# RelayCard.net
KiCad netlist of a schematic drawn in Altium Designer
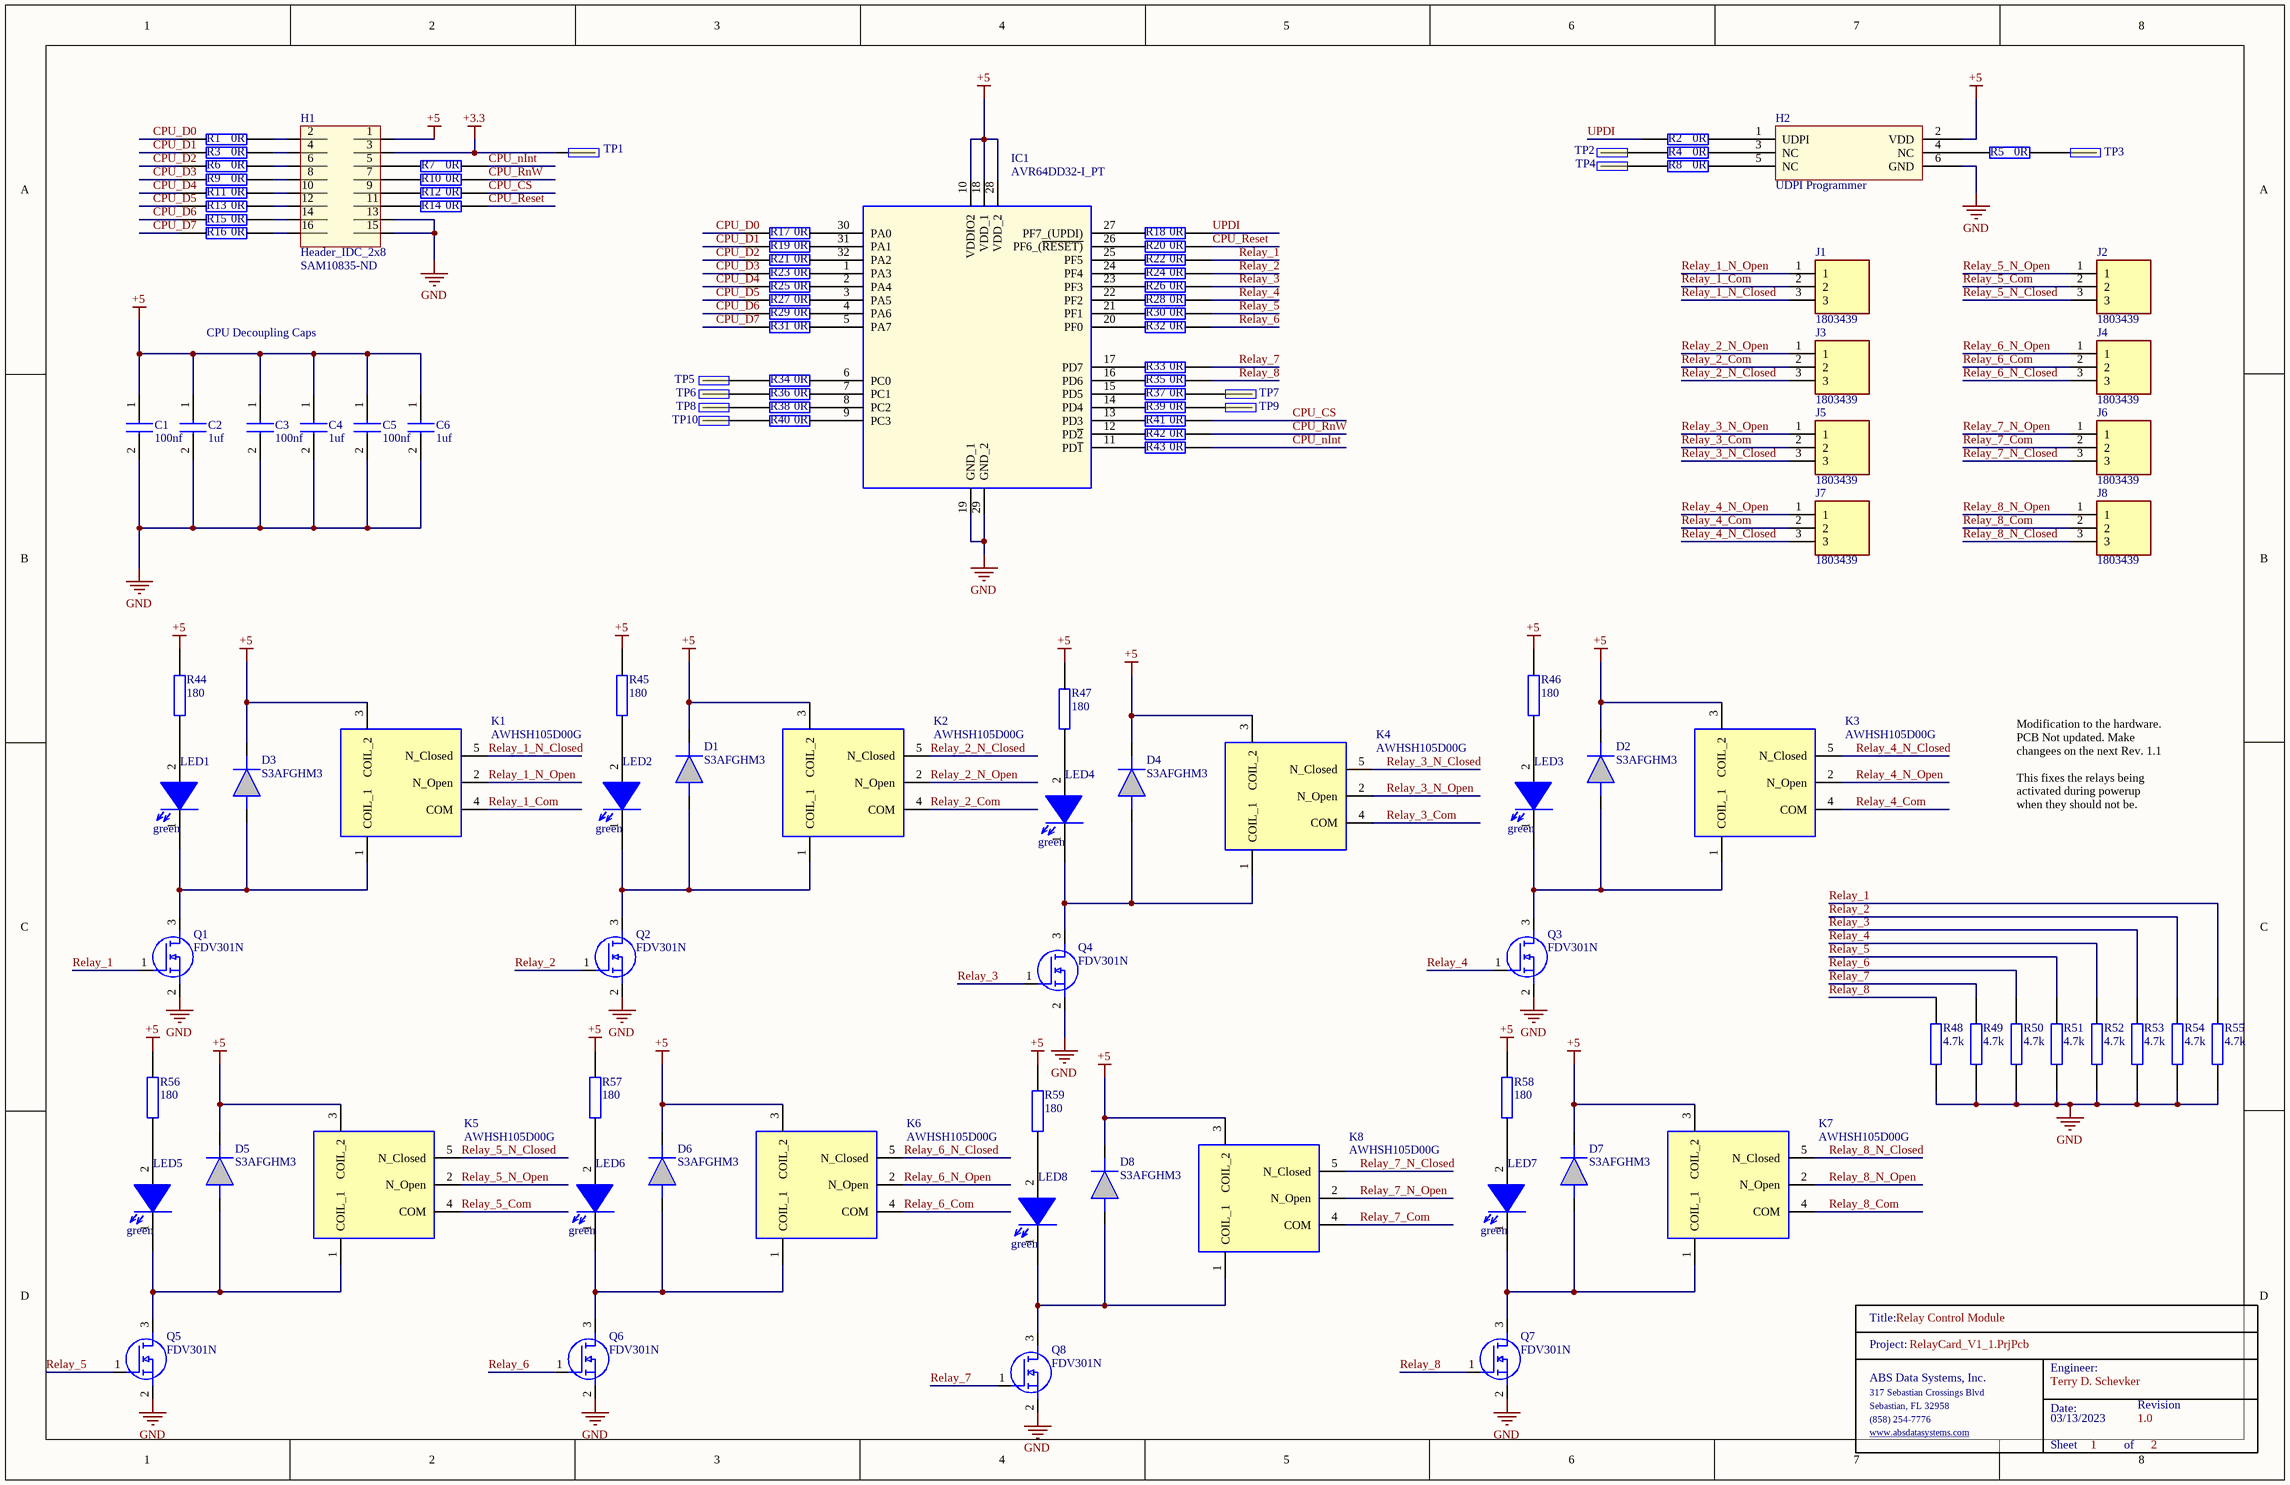
[diagram p0: RelayCard.SchDoc]

(export (version "E")
  (design (tool "Eeschema 10.0.6"))
  (components
    (comp (ref "C1")
      (value "100nf")
      (footprint "0603")
      (description "Samsung Electro-Mechanics 0603 100nf")
      (libsource (lib "Capacitors") (part "CL10B104JB8NNNC"))
    )
    (comp (ref "C2")
      (value "1uf")
      (footprint "0603")
      (description "Samsung Electro-Mechanics 0603 1uf")
      (libsource (lib "Capacitors") (part "CL10B105KA8NNNL"))
    )
    (comp (ref "C3")
      (value "100nf")
      (footprint "0603")
      (description "Samsung Electro-Mechanics 0603 100nf")
      (libsource (lib "Capacitors") (part "CL10B104JB8NNNC"))
    )
    (comp (ref "C4")
      (value "1uf")
      (footprint "0603")
      (description "Samsung Electro-Mechanics 0603 1uf")
      (libsource (lib "Capacitors") (part "CL10B105KA8NNNL"))
    )
    (comp (ref "C5")
      (value "100nf")
      (footprint "0603")
      (description "Samsung Electro-Mechanics 0603 100nf")
      (libsource (lib "Capacitors") (part "CL10B104JB8NNNC"))
    )
    (comp (ref "C6")
      (value "1uf")
      (footprint "0603")
      (description "Samsung Electro-Mechanics 0603 1uf")
      (libsource (lib "Capacitors") (part "CL10B105KA8NNNL"))
    )
    (comp (ref "D1")
      (value "S3AFGHM3")
      (footprint "DO-221AC")
      (description "Rectifiers VR=400V, IO=3A")
      (fields
        (field (name "MOUSER PART NUMBER") "750-1N4001-G")
        (field (name "MANUFACTURER_PART_NUMBER") "1N4001-G")
      )
      (libsource (lib "SemiConductors") (part "S3AFGHM3/I"))
    )
    (comp (ref "D2")
      (value "S3AFGHM3")
      (footprint "DO-221AC")
      (description "Rectifiers VR=400V, IO=3A")
      (fields
        (field (name "MOUSER PART NUMBER") "750-1N4001-G")
        (field (name "MANUFACTURER_PART_NUMBER") "1N4001-G")
      )
      (libsource (lib "SemiConductors") (part "S3AFGHM3/I"))
    )
    (comp (ref "D3")
      (value "S3AFGHM3")
      (footprint "DO-221AC")
      (description "Rectifiers VR=400V, IO=3A")
      (fields
        (field (name "MOUSER PART NUMBER") "750-1N4001-G")
        (field (name "MANUFACTURER_PART_NUMBER") "1N4001-G")
      )
      (libsource (lib "SemiConductors") (part "S3AFGHM3/I"))
    )
    (comp (ref "D4")
      (value "S3AFGHM3")
      (footprint "DO-221AC")
      (description "Rectifiers VR=400V, IO=3A")
      (fields
        (field (name "MOUSER PART NUMBER") "750-1N4001-G")
        (field (name "MANUFACTURER_PART_NUMBER") "1N4001-G")
      )
      (libsource (lib "SemiConductors") (part "S3AFGHM3/I"))
    )
    (comp (ref "D5")
      (value "S3AFGHM3")
      (footprint "DO-221AC")
      (description "Rectifiers VR=400V, IO=3A")
      (fields
        (field (name "MOUSER PART NUMBER") "750-1N4001-G")
        (field (name "MANUFACTURER_PART_NUMBER") "1N4001-G")
      )
      (libsource (lib "SemiConductors") (part "S3AFGHM3/I"))
    )
    (comp (ref "D6")
      (value "S3AFGHM3")
      (footprint "DO-221AC")
      (description "Rectifiers VR=400V, IO=3A")
      (fields
        (field (name "MOUSER PART NUMBER") "750-1N4001-G")
        (field (name "MANUFACTURER_PART_NUMBER") "1N4001-G")
      )
      (libsource (lib "SemiConductors") (part "S3AFGHM3/I"))
    )
    (comp (ref "D7")
      (value "S3AFGHM3")
      (footprint "DO-221AC")
      (description "Rectifiers VR=400V, IO=3A")
      (fields
        (field (name "MOUSER PART NUMBER") "750-1N4001-G")
        (field (name "MANUFACTURER_PART_NUMBER") "1N4001-G")
      )
      (libsource (lib "SemiConductors") (part "S3AFGHM3/I"))
    )
    (comp (ref "D8")
      (value "S3AFGHM3")
      (footprint "DO-221AC")
      (description "Rectifiers VR=400V, IO=3A")
      (fields
        (field (name "MOUSER PART NUMBER") "750-1N4001-G")
        (field (name "MANUFACTURER_PART_NUMBER") "1N4001-G")
      )
      (libsource (lib "SemiConductors") (part "S3AFGHM3/I"))
    )
    (comp (ref "H1")
      (value "Header_IDC_2x8")
      (footprint "HEADER16")
      (description "16 Pin 2x8 Through Hold IDC Connector")
      (fields
        (field (name "MANUFACTURER") "Samtec")
        (field (name "MANUFACTURER PART NUMBER") "TST-108-01-G-D")
        (field (name "SUPPLIER PART NUMBER 1") "SAM10835-ND")
      )
      (libsource (lib "Misc") (part "Header_IDC_2x8"))
    )
    (comp (ref "H2")
      (value "UDPI Programmer")
      (footprint "HDR2X3")
      (description "6 Pin 2X3 Through Hole Header")
      (libsource (lib "Misc") (part "UDPI Programmer"))
    )
    (comp (ref "IC1")
      (value "AVR64DD32-I_PT")
      (footprint "CPU_Memory:QFP80P900X900X120-32N")
      (description "Integrated Circuit")
      (fields (field (name "MANUFACTURER_PART_NUMBER") "AVR64DD32-I/PT ¦ MULTI-VOLTAGE I/O"))
      (libsource (lib "CPU_Memory") (part "AVR64DD32-I_PT"))
    )
    (comp (ref "J1")
      (value "1803439")
      (footprint "SamacSys:1803439")
      (description "Connector")
      (fields (field (name "MOUSER PART NUMBER") "651-1803439"))
      (libsource (lib "*") (part "1803439"))
    )
    (comp (ref "J2")
      (value "1803439")
      (footprint "SamacSys:1803439")
      (description "Connector")
      (fields (field (name "MOUSER PART NUMBER") "651-1803439"))
      (libsource (lib "*") (part "1803439"))
    )
    (comp (ref "J3")
      (value "1803439")
      (footprint "SamacSys:1803439")
      (description "Connector")
      (fields (field (name "MOUSER PART NUMBER") "651-1803439"))
      (libsource (lib "*") (part "1803439"))
    )
    (comp (ref "J4")
      (value "1803439")
      (footprint "SamacSys:1803439")
      (description "Connector")
      (fields (field (name "MOUSER PART NUMBER") "651-1803439"))
      (libsource (lib "*") (part "1803439"))
    )
    (comp (ref "J5")
      (value "1803439")
      (footprint "SamacSys:1803439")
      (description "Connector")
      (fields (field (name "MOUSER PART NUMBER") "651-1803439"))
      (libsource (lib "*") (part "1803439"))
    )
    (comp (ref "J6")
      (value "1803439")
      (footprint "SamacSys:1803439")
      (description "Connector")
      (fields (field (name "MOUSER PART NUMBER") "651-1803439"))
      (libsource (lib "*") (part "1803439"))
    )
    (comp (ref "J7")
      (value "1803439")
      (footprint "SamacSys:1803439")
      (description "Connector")
      (fields (field (name "MOUSER PART NUMBER") "651-1803439"))
      (libsource (lib "*") (part "1803439"))
    )
    (comp (ref "J8")
      (value "1803439")
      (footprint "SamacSys:1803439")
      (description "Connector")
      (fields (field (name "MOUSER PART NUMBER") "651-1803439"))
      (libsource (lib "*") (part "1803439"))
    )
    (comp (ref "K1")
      (value "AWHSH105D00G")
      (footprint "AWHSH105D00G")
      (fields (field (name "MOUSER PART NUMBER") "523-AWHSH105D00G"))
      (libsource (lib "Misc") (part "AWHSH105D00G"))
    )
    (comp (ref "K2")
      (value "AWHSH105D00G")
      (footprint "AWHSH105D00G")
      (fields (field (name "MOUSER PART NUMBER") "523-AWHSH105D00G"))
      (libsource (lib "Misc") (part "AWHSH105D00G"))
    )
    (comp (ref "K3")
      (value "AWHSH105D00G")
      (footprint "AWHSH105D00G")
      (fields (field (name "MOUSER PART NUMBER") "523-AWHSH105D00G"))
      (libsource (lib "Misc") (part "AWHSH105D00G"))
    )
    (comp (ref "K4")
      (value "AWHSH105D00G")
      (footprint "AWHSH105D00G")
      (fields (field (name "MOUSER PART NUMBER") "523-AWHSH105D00G"))
      (libsource (lib "Misc") (part "AWHSH105D00G"))
    )
    (comp (ref "K5")
      (value "AWHSH105D00G")
      (footprint "AWHSH105D00G")
      (fields (field (name "MOUSER PART NUMBER") "523-AWHSH105D00G"))
      (libsource (lib "Misc") (part "AWHSH105D00G"))
    )
    (comp (ref "K6")
      (value "AWHSH105D00G")
      (footprint "AWHSH105D00G")
      (fields (field (name "MOUSER PART NUMBER") "523-AWHSH105D00G"))
      (libsource (lib "Misc") (part "AWHSH105D00G"))
    )
    (comp (ref "K7")
      (value "AWHSH105D00G")
      (footprint "AWHSH105D00G")
      (fields (field (name "MOUSER PART NUMBER") "523-AWHSH105D00G"))
      (libsource (lib "Misc") (part "AWHSH105D00G"))
    )
    (comp (ref "K8")
      (value "AWHSH105D00G")
      (footprint "AWHSH105D00G")
      (fields (field (name "MOUSER PART NUMBER") "523-AWHSH105D00G"))
      (libsource (lib "Misc") (part "AWHSH105D00G"))
    )
    (comp (ref "LED1")
      (value "green")
      (footprint "0603_Diode")
      (description "Wurth Elektronik 0603 green")
      (fields
        (field (name "MANUFACTURER") "Wurth Electronics")
        (field (name "MANUFACTURER PART NUMBER") "150060GS75000")
      )
      (libsource (lib "Misc") (part "150060GS75000"))
    )
    (comp (ref "LED2")
      (value "green")
      (footprint "0603_Diode")
      (description "Wurth Elektronik 0603 green")
      (fields
        (field (name "MANUFACTURER") "Wurth Electronics")
        (field (name "MANUFACTURER PART NUMBER") "150060GS75000")
      )
      (libsource (lib "Misc") (part "150060GS75000"))
    )
    (comp (ref "LED3")
      (value "green")
      (footprint "0603_Diode")
      (description "Wurth Elektronik 0603 green")
      (fields
        (field (name "MANUFACTURER") "Wurth Electronics")
        (field (name "MANUFACTURER PART NUMBER") "150060GS75000")
      )
      (libsource (lib "Misc") (part "150060GS75000"))
    )
    (comp (ref "LED4")
      (value "green")
      (footprint "0603_Diode")
      (description "Wurth Elektronik 0603 green")
      (fields
        (field (name "MANUFACTURER") "Wurth Electronics")
        (field (name "MANUFACTURER PART NUMBER") "150060GS75000")
      )
      (libsource (lib "Misc") (part "150060GS75000"))
    )
    (comp (ref "LED5")
      (value "green")
      (footprint "0603_Diode")
      (description "Wurth Elektronik 0603 green")
      (fields
        (field (name "MANUFACTURER") "Wurth Electronics")
        (field (name "MANUFACTURER PART NUMBER") "150060GS75000")
      )
      (libsource (lib "Misc") (part "150060GS75000"))
    )
    (comp (ref "LED6")
      (value "green")
      (footprint "0603_Diode")
      (description "Wurth Elektronik 0603 green")
      (fields
        (field (name "MANUFACTURER") "Wurth Electronics")
        (field (name "MANUFACTURER PART NUMBER") "150060GS75000")
      )
      (libsource (lib "Misc") (part "150060GS75000"))
    )
    (comp (ref "LED7")
      (value "green")
      (footprint "0603_Diode")
      (description "Wurth Elektronik 0603 green")
      (fields
        (field (name "MANUFACTURER") "Wurth Electronics")
        (field (name "MANUFACTURER PART NUMBER") "150060GS75000")
      )
      (libsource (lib "Misc") (part "150060GS75000"))
    )
    (comp (ref "LED8")
      (value "green")
      (footprint "0603_Diode")
      (description "Wurth Elektronik 0603 green")
      (fields
        (field (name "MANUFACTURER") "Wurth Electronics")
        (field (name "MANUFACTURER PART NUMBER") "150060GS75000")
      )
      (libsource (lib "Misc") (part "150060GS75000"))
    )
    (comp (ref "Q1")
      (value "FDV301N")
      (footprint "SOT96P237X111-3N")
      (fields (field (name "MOUSER PART NUMBER") "512-FDV301N"))
      (libsource (lib "SemiConductors") (part "FDV301N"))
    )
    (comp (ref "Q2")
      (value "FDV301N")
      (footprint "SOT96P237X111-3N")
      (fields (field (name "MOUSER PART NUMBER") "512-FDV301N"))
      (libsource (lib "SemiConductors") (part "FDV301N"))
    )
    (comp (ref "Q3")
      (value "FDV301N")
      (footprint "SOT96P237X111-3N")
      (fields (field (name "MOUSER PART NUMBER") "512-FDV301N"))
      (libsource (lib "SemiConductors") (part "FDV301N"))
    )
    (comp (ref "Q4")
      (value "FDV301N")
      (footprint "SOT96P237X111-3N")
      (fields (field (name "MOUSER PART NUMBER") "512-FDV301N"))
      (libsource (lib "SemiConductors") (part "FDV301N"))
    )
    (comp (ref "Q5")
      (value "FDV301N")
      (footprint "SOT96P237X111-3N")
      (fields (field (name "MOUSER PART NUMBER") "512-FDV301N"))
      (libsource (lib "SemiConductors") (part "FDV301N"))
    )
    (comp (ref "Q6")
      (value "FDV301N")
      (footprint "SOT96P237X111-3N")
      (fields (field (name "MOUSER PART NUMBER") "512-FDV301N"))
      (libsource (lib "SemiConductors") (part "FDV301N"))
    )
    (comp (ref "Q7")
      (value "FDV301N")
      (footprint "SOT96P237X111-3N")
      (fields (field (name "MOUSER PART NUMBER") "512-FDV301N"))
      (libsource (lib "SemiConductors") (part "FDV301N"))
    )
    (comp (ref "Q8")
      (value "FDV301N")
      (footprint "SOT96P237X111-3N")
      (fields (field (name "MOUSER PART NUMBER") "512-FDV301N"))
      (libsource (lib "SemiConductors") (part "FDV301N"))
    )
    (comp (ref "R1")
      (value "0R")
      (footprint "0603")
      (description "YAGEO 0603 0 ohm")
      (fields
        (field (name "MOUSER PART NUMBER") "603-RC0603JR-070RL")
        (field (name "MANUFACTURER_PART_NUMBER") "RC0603JR-070RL")
      )
      (libsource (lib "Resistors") (part "RC0603JR-070RL"))
    )
    (comp (ref "R2")
      (value "0R")
      (footprint "0603")
      (description "YAGEO 0603 0 ohm")
      (fields
        (field (name "MOUSER PART NUMBER") "603-RC0603JR-070RL")
        (field (name "MANUFACTURER_PART_NUMBER") "RC0603JR-070RL")
      )
      (libsource (lib "Resistors") (part "RC0603JR-070RL"))
    )
    (comp (ref "R3")
      (value "0R")
      (footprint "0603")
      (description "YAGEO 0603 0 ohm")
      (fields
        (field (name "MOUSER PART NUMBER") "603-RC0603JR-070RL")
        (field (name "MANUFACTURER_PART_NUMBER") "RC0603JR-070RL")
      )
      (libsource (lib "Resistors") (part "RC0603JR-070RL"))
    )
    (comp (ref "R4")
      (value "0R")
      (footprint "0603")
      (description "YAGEO 0603 0 ohm")
      (fields
        (field (name "MOUSER PART NUMBER") "603-RC0603JR-070RL")
        (field (name "MANUFACTURER_PART_NUMBER") "RC0603JR-070RL")
      )
      (libsource (lib "Resistors") (part "RC0603JR-070RL"))
    )
    (comp (ref "R5")
      (value "0R")
      (footprint "0603")
      (description "YAGEO 0603 0 ohm")
      (fields
        (field (name "MOUSER PART NUMBER") "603-RC0603JR-070RL")
        (field (name "MANUFACTURER_PART_NUMBER") "RC0603JR-070RL")
      )
      (libsource (lib "Resistors") (part "RC0603JR-070RL"))
    )
    (comp (ref "R6")
      (value "0R")
      (footprint "0603")
      (description "YAGEO 0603 0 ohm")
      (fields
        (field (name "MOUSER PART NUMBER") "603-RC0603JR-070RL")
        (field (name "MANUFACTURER_PART_NUMBER") "RC0603JR-070RL")
      )
      (libsource (lib "Resistors") (part "RC0603JR-070RL"))
    )
    (comp (ref "R7")
      (value "0R")
      (footprint "0603")
      (description "YAGEO 0603 0 ohm")
      (fields
        (field (name "MOUSER PART NUMBER") "603-RC0603JR-070RL")
        (field (name "MANUFACTURER_PART_NUMBER") "RC0603JR-070RL")
      )
      (libsource (lib "Resistors") (part "RC0603JR-070RL"))
    )
    (comp (ref "R8")
      (value "0R")
      (footprint "0603")
      (description "YAGEO 0603 0 ohm")
      (fields
        (field (name "MOUSER PART NUMBER") "603-RC0603JR-070RL")
        (field (name "MANUFACTURER_PART_NUMBER") "RC0603JR-070RL")
      )
      (libsource (lib "Resistors") (part "RC0603JR-070RL"))
    )
    (comp (ref "R9")
      (value "0R")
      (footprint "0603")
      (description "YAGEO 0603 0 ohm")
      (fields
        (field (name "MOUSER PART NUMBER") "603-RC0603JR-070RL")
        (field (name "MANUFACTURER_PART_NUMBER") "RC0603JR-070RL")
      )
      (libsource (lib "Resistors") (part "RC0603JR-070RL"))
    )
    (comp (ref "R10")
      (value "0R")
      (footprint "0603")
      (description "YAGEO 0603 0 ohm")
      (fields
        (field (name "MOUSER PART NUMBER") "603-RC0603JR-070RL")
        (field (name "MANUFACTURER_PART_NUMBER") "RC0603JR-070RL")
      )
      (libsource (lib "Resistors") (part "RC0603JR-070RL"))
    )
    (comp (ref "R11")
      (value "0R")
      (footprint "0603")
      (description "YAGEO 0603 0 ohm")
      (fields
        (field (name "MOUSER PART NUMBER") "603-RC0603JR-070RL")
        (field (name "MANUFACTURER_PART_NUMBER") "RC0603JR-070RL")
      )
      (libsource (lib "Resistors") (part "RC0603JR-070RL"))
    )
    (comp (ref "R12")
      (value "0R")
      (footprint "0603")
      (description "YAGEO 0603 0 ohm")
      (fields
        (field (name "MOUSER PART NUMBER") "603-RC0603JR-070RL")
        (field (name "MANUFACTURER_PART_NUMBER") "RC0603JR-070RL")
      )
      (libsource (lib "Resistors") (part "RC0603JR-070RL"))
    )
    (comp (ref "R13")
      (value "0R")
      (footprint "0603")
      (description "YAGEO 0603 0 ohm")
      (fields
        (field (name "MOUSER PART NUMBER") "603-RC0603JR-070RL")
        (field (name "MANUFACTURER_PART_NUMBER") "RC0603JR-070RL")
      )
      (libsource (lib "Resistors") (part "RC0603JR-070RL"))
    )
    (comp (ref "R14")
      (value "0R")
      (footprint "0603")
      (description "YAGEO 0603 0 ohm")
      (fields
        (field (name "MOUSER PART NUMBER") "603-RC0603JR-070RL")
        (field (name "MANUFACTURER_PART_NUMBER") "RC0603JR-070RL")
      )
      (libsource (lib "Resistors") (part "RC0603JR-070RL"))
    )
    (comp (ref "R15")
      (value "0R")
      (footprint "0603")
      (description "YAGEO 0603 0 ohm")
      (fields
        (field (name "MOUSER PART NUMBER") "603-RC0603JR-070RL")
        (field (name "MANUFACTURER_PART_NUMBER") "RC0603JR-070RL")
      )
      (libsource (lib "Resistors") (part "RC0603JR-070RL"))
    )
    (comp (ref "R16")
      (value "0R")
      (footprint "0603")
      (description "YAGEO 0603 0 ohm")
      (fields
        (field (name "MOUSER PART NUMBER") "603-RC0603JR-070RL")
        (field (name "MANUFACTURER_PART_NUMBER") "RC0603JR-070RL")
      )
      (libsource (lib "Resistors") (part "RC0603JR-070RL"))
    )
    (comp (ref "R17")
      (value "0R")
      (footprint "0603")
      (description "YAGEO 0603 0 ohm")
      (fields
        (field (name "MOUSER PART NUMBER") "603-RC0603JR-070RL")
        (field (name "MANUFACTURER_PART_NUMBER") "RC0603JR-070RL")
      )
      (libsource (lib "Resistors") (part "RC0603JR-070RL"))
    )
    (comp (ref "R18")
      (value "0R")
      (footprint "0603")
      (description "YAGEO 0603 0 ohm")
      (fields
        (field (name "MOUSER PART NUMBER") "603-RC0603JR-070RL")
        (field (name "MANUFACTURER_PART_NUMBER") "RC0603JR-070RL")
      )
      (libsource (lib "Resistors") (part "RC0603JR-070RL"))
    )
    (comp (ref "R19")
      (value "0R")
      (footprint "0603")
      (description "YAGEO 0603 0 ohm")
      (fields
        (field (name "MOUSER PART NUMBER") "603-RC0603JR-070RL")
        (field (name "MANUFACTURER_PART_NUMBER") "RC0603JR-070RL")
      )
      (libsource (lib "Resistors") (part "RC0603JR-070RL"))
    )
    (comp (ref "R20")
      (value "0R")
      (footprint "0603")
      (description "YAGEO 0603 0 ohm")
      (fields
        (field (name "MOUSER PART NUMBER") "603-RC0603JR-070RL")
        (field (name "MANUFACTURER_PART_NUMBER") "RC0603JR-070RL")
      )
      (libsource (lib "Resistors") (part "RC0603JR-070RL"))
    )
    (comp (ref "R21")
      (value "0R")
      (footprint "0603")
      (description "YAGEO 0603 0 ohm")
      (fields
        (field (name "MOUSER PART NUMBER") "603-RC0603JR-070RL")
        (field (name "MANUFACTURER_PART_NUMBER") "RC0603JR-070RL")
      )
      (libsource (lib "Resistors") (part "RC0603JR-070RL"))
    )
    (comp (ref "R22")
      (value "0R")
      (footprint "0603")
      (description "YAGEO 0603 0 ohm")
      (fields
        (field (name "MOUSER PART NUMBER") "603-RC0603JR-070RL")
        (field (name "MANUFACTURER_PART_NUMBER") "RC0603JR-070RL")
      )
      (libsource (lib "Resistors") (part "RC0603JR-070RL"))
    )
    (comp (ref "R23")
      (value "0R")
      (footprint "0603")
      (description "YAGEO 0603 0 ohm")
      (fields
        (field (name "MOUSER PART NUMBER") "603-RC0603JR-070RL")
        (field (name "MANUFACTURER_PART_NUMBER") "RC0603JR-070RL")
      )
      (libsource (lib "Resistors") (part "RC0603JR-070RL"))
    )
    (comp (ref "R24")
      (value "0R")
      (footprint "0603")
      (description "YAGEO 0603 0 ohm")
      (fields
        (field (name "MOUSER PART NUMBER") "603-RC0603JR-070RL")
        (field (name "MANUFACTURER_PART_NUMBER") "RC0603JR-070RL")
      )
      (libsource (lib "Resistors") (part "RC0603JR-070RL"))
    )
    (comp (ref "R25")
      (value "0R")
      (footprint "0603")
      (description "YAGEO 0603 0 ohm")
      (fields
        (field (name "MOUSER PART NUMBER") "603-RC0603JR-070RL")
        (field (name "MANUFACTURER_PART_NUMBER") "RC0603JR-070RL")
      )
      (libsource (lib "Resistors") (part "RC0603JR-070RL"))
    )
    (comp (ref "R26")
      (value "0R")
      (footprint "0603")
      (description "YAGEO 0603 0 ohm")
      (fields
        (field (name "MOUSER PART NUMBER") "603-RC0603JR-070RL")
        (field (name "MANUFACTURER_PART_NUMBER") "RC0603JR-070RL")
      )
      (libsource (lib "Resistors") (part "RC0603JR-070RL"))
    )
    (comp (ref "R27")
      (value "0R")
      (footprint "0603")
      (description "YAGEO 0603 0 ohm")
      (fields
        (field (name "MOUSER PART NUMBER") "603-RC0603JR-070RL")
        (field (name "MANUFACTURER_PART_NUMBER") "RC0603JR-070RL")
      )
      (libsource (lib "Resistors") (part "RC0603JR-070RL"))
    )
    (comp (ref "R28")
      (value "0R")
      (footprint "0603")
      (description "YAGEO 0603 0 ohm")
      (fields
        (field (name "MOUSER PART NUMBER") "603-RC0603JR-070RL")
        (field (name "MANUFACTURER_PART_NUMBER") "RC0603JR-070RL")
      )
      (libsource (lib "Resistors") (part "RC0603JR-070RL"))
    )
    (comp (ref "R29")
      (value "0R")
      (footprint "0603")
      (description "YAGEO 0603 0 ohm")
      (fields
        (field (name "MOUSER PART NUMBER") "603-RC0603JR-070RL")
        (field (name "MANUFACTURER_PART_NUMBER") "RC0603JR-070RL")
      )
      (libsource (lib "Resistors") (part "RC0603JR-070RL"))
    )
    (comp (ref "R30")
      (value "0R")
      (footprint "0603")
      (description "YAGEO 0603 0 ohm")
      (fields
        (field (name "MOUSER PART NUMBER") "603-RC0603JR-070RL")
        (field (name "MANUFACTURER_PART_NUMBER") "RC0603JR-070RL")
      )
      (libsource (lib "Resistors") (part "RC0603JR-070RL"))
    )
    (comp (ref "R31")
      (value "0R")
      (footprint "0603")
      (description "YAGEO 0603 0 ohm")
      (fields
        (field (name "MOUSER PART NUMBER") "603-RC0603JR-070RL")
        (field (name "MANUFACTURER_PART_NUMBER") "RC0603JR-070RL")
      )
      (libsource (lib "Resistors") (part "RC0603JR-070RL"))
    )
    (comp (ref "R32")
      (value "0R")
      (footprint "0603")
      (description "YAGEO 0603 0 ohm")
      (fields
        (field (name "MOUSER PART NUMBER") "603-RC0603JR-070RL")
        (field (name "MANUFACTURER_PART_NUMBER") "RC0603JR-070RL")
      )
      (libsource (lib "Resistors") (part "RC0603JR-070RL"))
    )
    (comp (ref "R33")
      (value "0R")
      (footprint "0603")
      (description "YAGEO 0603 0 ohm")
      (fields
        (field (name "MOUSER PART NUMBER") "603-RC0603JR-070RL")
        (field (name "MANUFACTURER_PART_NUMBER") "RC0603JR-070RL")
      )
      (libsource (lib "Resistors") (part "RC0603JR-070RL"))
    )
    (comp (ref "R34")
      (value "0R")
      (footprint "0603")
      (description "YAGEO 0603 0 ohm")
      (fields
        (field (name "MOUSER PART NUMBER") "603-RC0603JR-070RL")
        (field (name "MANUFACTURER_PART_NUMBER") "RC0603JR-070RL")
      )
      (libsource (lib "Resistors") (part "RC0603JR-070RL"))
    )
    (comp (ref "R35")
      (value "0R")
      (footprint "0603")
      (description "YAGEO 0603 0 ohm")
      (fields
        (field (name "MOUSER PART NUMBER") "603-RC0603JR-070RL")
        (field (name "MANUFACTURER_PART_NUMBER") "RC0603JR-070RL")
      )
      (libsource (lib "Resistors") (part "RC0603JR-070RL"))
    )
    (comp (ref "R36")
      (value "0R")
      (footprint "0603")
      (description "YAGEO 0603 0 ohm")
      (fields
        (field (name "MOUSER PART NUMBER") "603-RC0603JR-070RL")
        (field (name "MANUFACTURER_PART_NUMBER") "RC0603JR-070RL")
      )
      (libsource (lib "Resistors") (part "RC0603JR-070RL"))
    )
    (comp (ref "R37")
      (value "0R")
      (footprint "0603")
      (description "YAGEO 0603 0 ohm")
      (fields
        (field (name "MOUSER PART NUMBER") "603-RC0603JR-070RL")
        (field (name "MANUFACTURER_PART_NUMBER") "RC0603JR-070RL")
      )
      (libsource (lib "Resistors") (part "RC0603JR-070RL"))
    )
    (comp (ref "R38")
      (value "0R")
      (footprint "0603")
      (description "YAGEO 0603 0 ohm")
      (fields
        (field (name "MOUSER PART NUMBER") "603-RC0603JR-070RL")
        (field (name "MANUFACTURER_PART_NUMBER") "RC0603JR-070RL")
      )
      (libsource (lib "Resistors") (part "RC0603JR-070RL"))
    )
    (comp (ref "R39")
      (value "0R")
      (footprint "0603")
      (description "YAGEO 0603 0 ohm")
      (fields
        (field (name "MOUSER PART NUMBER") "603-RC0603JR-070RL")
        (field (name "MANUFACTURER_PART_NUMBER") "RC0603JR-070RL")
      )
      (libsource (lib "Resistors") (part "RC0603JR-070RL"))
    )
    (comp (ref "R40")
      (value "0R")
      (footprint "0603")
      (description "YAGEO 0603 0 ohm")
      (fields
        (field (name "MOUSER PART NUMBER") "603-RC0603JR-070RL")
        (field (name "MANUFACTURER_PART_NUMBER") "RC0603JR-070RL")
      )
      (libsource (lib "Resistors") (part "RC0603JR-070RL"))
    )
    (comp (ref "R41")
      (value "0R")
      (footprint "0603")
      (description "YAGEO 0603 0 ohm")
      (fields
        (field (name "MOUSER PART NUMBER") "603-RC0603JR-070RL")
        (field (name "MANUFACTURER_PART_NUMBER") "RC0603JR-070RL")
      )
      (libsource (lib "Resistors") (part "RC0603JR-070RL"))
    )
    (comp (ref "R42")
      (value "0R")
      (footprint "0603")
      (description "YAGEO 0603 0 ohm")
      (fields
        (field (name "MOUSER PART NUMBER") "603-RC0603JR-070RL")
        (field (name "MANUFACTURER_PART_NUMBER") "RC0603JR-070RL")
      )
      (libsource (lib "Resistors") (part "RC0603JR-070RL"))
    )
    (comp (ref "R43")
      (value "0R")
      (footprint "0603")
      (description "YAGEO 0603 0 ohm")
      (fields
        (field (name "MOUSER PART NUMBER") "603-RC0603JR-070RL")
        (field (name "MANUFACTURER_PART_NUMBER") "RC0603JR-070RL")
      )
      (libsource (lib "Resistors") (part "RC0603JR-070RL"))
    )
    (comp (ref "R44")
      (value "180")
      (footprint "0603")
      (description "YAGEO 0603 180 ohm")
      (fields
        (field (name "MOUSER PART NUMBER") "603-RC0603JR-070RL")
        (field (name "MANUFACTURER_PART_NUMBER") "RC0603JR-070RL")
      )
      (libsource (lib "Resistors") (part "RC0603FR-13180RL"))
    )
    (comp (ref "R45")
      (value "180")
      (footprint "0603")
      (description "YAGEO 0603 180 ohm")
      (fields
        (field (name "MOUSER PART NUMBER") "603-RC0603JR-070RL")
        (field (name "MANUFACTURER_PART_NUMBER") "RC0603JR-070RL")
      )
      (libsource (lib "Resistors") (part "RC0603FR-13180RL"))
    )
    (comp (ref "R46")
      (value "180")
      (footprint "0603")
      (description "YAGEO 0603 180 ohm")
      (fields
        (field (name "MOUSER PART NUMBER") "603-RC0603JR-070RL")
        (field (name "MANUFACTURER_PART_NUMBER") "RC0603JR-070RL")
      )
      (libsource (lib "Resistors") (part "RC0603FR-13180RL"))
    )
    (comp (ref "R47")
      (value "180")
      (footprint "0603")
      (description "YAGEO 0603 180 ohm")
      (fields
        (field (name "MOUSER PART NUMBER") "603-RC0603JR-070RL")
        (field (name "MANUFACTURER_PART_NUMBER") "RC0603JR-070RL")
      )
      (libsource (lib "Resistors") (part "RC0603FR-13180RL"))
    )
    (comp (ref "R48")
      (value "4.7k")
      (footprint "Capacitors:0603")
      (description "YAGEO 0603 4.7k")
      (fields
        (field (name "MOUSER PART NUMBER") "603-RC0603JR-070RL")
        (field (name "MANUFACTURER_PART_NUMBER") "RC0603JR-070RL")
      )
      (libsource (lib "Resistors") (part "RC0603FR-104K7L"))
    )
    (comp (ref "R49")
      (value "4.7k")
      (footprint "Capacitors:0603")
      (description "YAGEO 0603 4.7k")
      (fields
        (field (name "MOUSER PART NUMBER") "603-RC0603JR-070RL")
        (field (name "MANUFACTURER_PART_NUMBER") "RC0603JR-070RL")
      )
      (libsource (lib "Resistors") (part "RC0603FR-104K7L"))
    )
    (comp (ref "R50")
      (value "4.7k")
      (footprint "Capacitors:0603")
      (description "YAGEO 0603 4.7k")
      (fields
        (field (name "MOUSER PART NUMBER") "603-RC0603JR-070RL")
        (field (name "MANUFACTURER_PART_NUMBER") "RC0603JR-070RL")
      )
      (libsource (lib "Resistors") (part "RC0603FR-104K7L"))
    )
    (comp (ref "R51")
      (value "4.7k")
      (footprint "Capacitors:0603")
      (description "YAGEO 0603 4.7k")
      (fields
        (field (name "MOUSER PART NUMBER") "603-RC0603JR-070RL")
        (field (name "MANUFACTURER_PART_NUMBER") "RC0603JR-070RL")
      )
      (libsource (lib "Resistors") (part "RC0603FR-104K7L"))
    )
    (comp (ref "R52")
      (value "4.7k")
      (footprint "Capacitors:0603")
      (description "YAGEO 0603 4.7k")
      (fields
        (field (name "MOUSER PART NUMBER") "603-RC0603JR-070RL")
        (field (name "MANUFACTURER_PART_NUMBER") "RC0603JR-070RL")
      )
      (libsource (lib "Resistors") (part "RC0603FR-104K7L"))
    )
    (comp (ref "R53")
      (value "4.7k")
      (footprint "Capacitors:0603")
      (description "YAGEO 0603 4.7k")
      (fields
        (field (name "MOUSER PART NUMBER") "603-RC0603JR-070RL")
        (field (name "MANUFACTURER_PART_NUMBER") "RC0603JR-070RL")
      )
      (libsource (lib "Resistors") (part "RC0603FR-104K7L"))
    )
    (comp (ref "R54")
      (value "4.7k")
      (footprint "Capacitors:0603")
      (description "YAGEO 0603 4.7k")
      (fields
        (field (name "MOUSER PART NUMBER") "603-RC0603JR-070RL")
        (field (name "MANUFACTURER_PART_NUMBER") "RC0603JR-070RL")
      )
      (libsource (lib "Resistors") (part "RC0603FR-104K7L"))
    )
    (comp (ref "R55")
      (value "4.7k")
      (footprint "Capacitors:0603")
      (description "YAGEO 0603 4.7k")
      (fields
        (field (name "MOUSER PART NUMBER") "603-RC0603JR-070RL")
        (field (name "MANUFACTURER_PART_NUMBER") "RC0603JR-070RL")
      )
      (libsource (lib "Resistors") (part "RC0603FR-104K7L"))
    )
    (comp (ref "R56")
      (value "180")
      (footprint "0603")
      (description "YAGEO 0603 180 ohm")
      (fields
        (field (name "MOUSER PART NUMBER") "603-RC0603JR-070RL")
        (field (name "MANUFACTURER_PART_NUMBER") "RC0603JR-070RL")
      )
      (libsource (lib "Resistors") (part "RC0603FR-13180RL"))
    )
    (comp (ref "R57")
      (value "180")
      (footprint "0603")
      (description "YAGEO 0603 180 ohm")
      (fields
        (field (name "MOUSER PART NUMBER") "603-RC0603JR-070RL")
        (field (name "MANUFACTURER_PART_NUMBER") "RC0603JR-070RL")
      )
      (libsource (lib "Resistors") (part "RC0603FR-13180RL"))
    )
    (comp (ref "R58")
      (value "180")
      (footprint "0603")
      (description "YAGEO 0603 180 ohm")
      (fields
        (field (name "MOUSER PART NUMBER") "603-RC0603JR-070RL")
        (field (name "MANUFACTURER_PART_NUMBER") "RC0603JR-070RL")
      )
      (libsource (lib "Resistors") (part "RC0603FR-13180RL"))
    )
    (comp (ref "R59")
      (value "180")
      (footprint "0603")
      (description "YAGEO 0603 180 ohm")
      (fields
        (field (name "MOUSER PART NUMBER") "603-RC0603JR-070RL")
        (field (name "MANUFACTURER_PART_NUMBER") "RC0603JR-070RL")
      )
      (libsource (lib "Resistors") (part "RC0603FR-13180RL"))
    )
    (comp (ref "TitleBlock_1") (value "TitleBlock") (libsource (lib "Misc") (part "TitleBlock")))
    (comp (ref "TP1")
      (value "TP")
      (footprint "TP")
      (fields
        (field (name "MANUFACTURER") "Samtec")
        (field (name "MANUFACTURER PART NUMBER") "TST-105-01-G-D")
      )
      (libsource (lib "Misc") (part "TP"))
    )
    (comp (ref "TP2")
      (value "TP")
      (footprint "TP")
      (fields
        (field (name "MANUFACTURER") "Samtec")
        (field (name "MANUFACTURER PART NUMBER") "TST-105-01-G-D")
      )
      (libsource (lib "") (part "TP_1"))
    )
    (comp (ref "TP3")
      (value "TP")
      (footprint "TP")
      (fields
        (field (name "MANUFACTURER") "Samtec")
        (field (name "MANUFACTURER PART NUMBER") "TST-105-01-G-D")
      )
      (libsource (lib "Misc") (part "TP"))
    )
    (comp (ref "TP4")
      (value "TP")
      (footprint "TP")
      (fields
        (field (name "MANUFACTURER") "Samtec")
        (field (name "MANUFACTURER PART NUMBER") "TST-105-01-G-D")
      )
      (libsource (lib "") (part "TP_1"))
    )
    (comp (ref "TP5")
      (value "TP")
      (footprint "TP")
      (fields
        (field (name "MANUFACTURER") "Samtec")
        (field (name "MANUFACTURER PART NUMBER") "TST-105-01-G-D")
      )
      (libsource (lib "") (part "TP_1"))
    )
    (comp (ref "TP6")
      (value "TP")
      (footprint "TP")
      (fields
        (field (name "MANUFACTURER") "Samtec")
        (field (name "MANUFACTURER PART NUMBER") "TST-105-01-G-D")
      )
      (libsource (lib "") (part "TP_1"))
    )
    (comp (ref "TP7")
      (value "TP")
      (footprint "TP")
      (fields
        (field (name "MANUFACTURER") "Samtec")
        (field (name "MANUFACTURER PART NUMBER") "TST-105-01-G-D")
      )
      (libsource (lib "Misc") (part "TP"))
    )
    (comp (ref "TP8")
      (value "TP")
      (footprint "TP")
      (fields
        (field (name "MANUFACTURER") "Samtec")
        (field (name "MANUFACTURER PART NUMBER") "TST-105-01-G-D")
      )
      (libsource (lib "") (part "TP_1"))
    )
    (comp (ref "TP9")
      (value "TP")
      (footprint "TP")
      (fields
        (field (name "MANUFACTURER") "Samtec")
        (field (name "MANUFACTURER PART NUMBER") "TST-105-01-G-D")
      )
      (libsource (lib "Misc") (part "TP"))
    )
    (comp (ref "TP10")
      (value "TP")
      (footprint "TP")
      (fields
        (field (name "MANUFACTURER") "Samtec")
        (field (name "MANUFACTURER PART NUMBER") "TST-105-01-G-D")
      )
      (libsource (lib "") (part "TP_1"))
    )
  )
  (nets
    (net (code "1") (name "+3.3") (class "Default")
      (node (ref "H1") (pin "3") (pinfunction "3_3") (pintype "passive"))
      (node (ref "TP1") (pin "1") (pinfunction "1_1") (pintype "passive"))
    )
    (net (code "2") (name "+5") (class "Default")
      (node (ref "C1") (pin "1") (pinfunction "1_1") (pintype "passive"))
      (node (ref "C2") (pin "1") (pinfunction "1_1") (pintype "passive"))
      (node (ref "C3") (pin "1") (pinfunction "1_1") (pintype "passive"))
      (node (ref "C4") (pin "1") (pinfunction "1_1") (pintype "passive"))
      (node (ref "C5") (pin "1") (pinfunction "1_1") (pintype "passive"))
      (node (ref "C6") (pin "1") (pinfunction "1_1") (pintype "passive"))
      (node (ref "D1") (pin "1") (pinfunction "K_1") (pintype "passive"))
      (node (ref "D2") (pin "1") (pinfunction "K_1") (pintype "passive"))
      (node (ref "D3") (pin "1") (pinfunction "K_1") (pintype "passive"))
      (node (ref "D4") (pin "1") (pinfunction "K_1") (pintype "passive"))
      (node (ref "D5") (pin "1") (pinfunction "K_1") (pintype "passive"))
      (node (ref "D6") (pin "1") (pinfunction "K_1") (pintype "passive"))
      (node (ref "D7") (pin "1") (pinfunction "K_1") (pintype "passive"))
      (node (ref "D8") (pin "1") (pinfunction "K_1") (pintype "passive"))
      (node (ref "H1") (pin "1") (pinfunction "1_1") (pintype "passive"))
      (node (ref "H2") (pin "2") (pinfunction "VDD_2") (pintype "passive"))
      (node (ref "IC1") (pin "10") (pinfunction "VDDIO2_10") (pintype "passive"))
      (node (ref "IC1") (pin "18") (pinfunction "VDD_1_18") (pintype "passive"))
      (node (ref "IC1") (pin "28") (pinfunction "VDD_2_28") (pintype "passive"))
      (node (ref "K1") (pin "3") (pinfunction "COIL_2_3") (pintype "passive"))
      (node (ref "K2") (pin "3") (pinfunction "COIL_2_3") (pintype "passive"))
      (node (ref "K3") (pin "3") (pinfunction "COIL_2_3") (pintype "passive"))
      (node (ref "K4") (pin "3") (pinfunction "COIL_2_3") (pintype "passive"))
      (node (ref "K5") (pin "3") (pinfunction "COIL_2_3") (pintype "passive"))
      (node (ref "K6") (pin "3") (pinfunction "COIL_2_3") (pintype "passive"))
      (node (ref "K7") (pin "3") (pinfunction "COIL_2_3") (pintype "passive"))
      (node (ref "K8") (pin "3") (pinfunction "COIL_2_3") (pintype "passive"))
      (node (ref "R44") (pin "2") (pinfunction "2_2") (pintype "passive"))
      (node (ref "R45") (pin "2") (pinfunction "2_2") (pintype "passive"))
      (node (ref "R46") (pin "2") (pinfunction "2_2") (pintype "passive"))
      (node (ref "R47") (pin "2") (pinfunction "2_2") (pintype "passive"))
      (node (ref "R56") (pin "2") (pinfunction "2_2") (pintype "passive"))
      (node (ref "R57") (pin "2") (pinfunction "2_2") (pintype "passive"))
      (node (ref "R58") (pin "2") (pinfunction "2_2") (pintype "passive"))
      (node (ref "R59") (pin "2") (pinfunction "2_2") (pintype "passive"))
    )
    (net (code "3") (name "/CPU_CS") (class "Default")
      (node (ref "R12") (pin "2") (pinfunction "2_2") (pintype "passive"))
      (node (ref "R41") (pin "2") (pinfunction "2_2") (pintype "passive"))
    )
    (net (code "4") (name "/CPU_D0") (class "Default")
      (node (ref "R1") (pin "1") (pinfunction "1_1") (pintype "passive"))
      (node (ref "R17") (pin "1") (pinfunction "1_1") (pintype "passive"))
    )
    (net (code "5") (name "/CPU_D1") (class "Default")
      (node (ref "R19") (pin "1") (pinfunction "1_1") (pintype "passive"))
      (node (ref "R3") (pin "1") (pinfunction "1_1") (pintype "passive"))
    )
    (net (code "6") (name "/CPU_D2") (class "Default")
      (node (ref "R21") (pin "1") (pinfunction "1_1") (pintype "passive"))
      (node (ref "R6") (pin "1") (pinfunction "1_1") (pintype "passive"))
    )
    (net (code "7") (name "/CPU_D3") (class "Default")
      (node (ref "R23") (pin "1") (pinfunction "1_1") (pintype "passive"))
      (node (ref "R9") (pin "1") (pinfunction "1_1") (pintype "passive"))
    )
    (net (code "8") (name "/CPU_D4") (class "Default")
      (node (ref "R11") (pin "1") (pinfunction "1_1") (pintype "passive"))
      (node (ref "R25") (pin "1") (pinfunction "1_1") (pintype "passive"))
    )
    (net (code "9") (name "/CPU_D5") (class "Default")
      (node (ref "R13") (pin "1") (pinfunction "1_1") (pintype "passive"))
      (node (ref "R27") (pin "1") (pinfunction "1_1") (pintype "passive"))
    )
    (net (code "10") (name "/CPU_D6") (class "Default")
      (node (ref "R15") (pin "1") (pinfunction "1_1") (pintype "passive"))
      (node (ref "R29") (pin "1") (pinfunction "1_1") (pintype "passive"))
    )
    (net (code "11") (name "/CPU_D7") (class "Default")
      (node (ref "R16") (pin "1") (pinfunction "1_1") (pintype "passive"))
      (node (ref "R31") (pin "1") (pinfunction "1_1") (pintype "passive"))
    )
    (net (code "12") (name "/CPU_Reset") (class "Default")
      (node (ref "R14") (pin "2") (pinfunction "2_2") (pintype "passive"))
      (node (ref "R20") (pin "2") (pinfunction "2_2") (pintype "passive"))
    )
    (net (code "13") (name "/CPU_RnW") (class "Default")
      (node (ref "R10") (pin "2") (pinfunction "2_2") (pintype "passive"))
      (node (ref "R42") (pin "2") (pinfunction "2_2") (pintype "passive"))
    )
    (net (code "14") (name "/CPU_nInt") (class "Default")
      (node (ref "R43") (pin "2") (pinfunction "2_2") (pintype "passive"))
      (node (ref "R7") (pin "2") (pinfunction "2_2") (pintype "passive"))
    )
    (net (code "15") (name "/Relay_1") (class "Default")
      (node (ref "Q1") (pin "1") (pinfunction "G_1") (pintype "passive"))
      (node (ref "R22") (pin "2") (pinfunction "2_2") (pintype "passive"))
      (node (ref "R55") (pin "1") (pinfunction "1_1") (pintype "passive"))
    )
    (net (code "16") (name "/Relay_1_Com") (class "Default")
      (node (ref "J1") (pin "2") (pinfunction "2_2") (pintype "passive"))
      (node (ref "K1") (pin "4") (pinfunction "COM_4") (pintype "passive"))
    )
    (net (code "17") (name "/Relay_1_N_Closed") (class "Default")
      (node (ref "J1") (pin "3") (pinfunction "3_3") (pintype "passive"))
      (node (ref "K1") (pin "5") (pinfunction "N_Closed_5") (pintype "passive"))
    )
    (net (code "18") (name "/Relay_1_N_Open") (class "Default")
      (node (ref "J1") (pin "1") (pinfunction "1_1") (pintype "passive"))
      (node (ref "K1") (pin "2") (pinfunction "N_Open_2") (pintype "passive"))
    )
    (net (code "19") (name "/Relay_2") (class "Default")
      (node (ref "Q2") (pin "1") (pinfunction "G_1") (pintype "passive"))
      (node (ref "R24") (pin "2") (pinfunction "2_2") (pintype "passive"))
      (node (ref "R54") (pin "1") (pinfunction "1_1") (pintype "passive"))
    )
    (net (code "20") (name "/Relay_2_Com") (class "Default")
      (node (ref "J3") (pin "2") (pinfunction "2_2") (pintype "passive"))
      (node (ref "K2") (pin "4") (pinfunction "COM_4") (pintype "passive"))
    )
    (net (code "21") (name "/Relay_2_N_Closed") (class "Default")
      (node (ref "J3") (pin "3") (pinfunction "3_3") (pintype "passive"))
      (node (ref "K2") (pin "5") (pinfunction "N_Closed_5") (pintype "passive"))
    )
    (net (code "22") (name "/Relay_2_N_Open") (class "Default")
      (node (ref "J3") (pin "1") (pinfunction "1_1") (pintype "passive"))
      (node (ref "K2") (pin "2") (pinfunction "N_Open_2") (pintype "passive"))
    )
    (net (code "23") (name "/Relay_3") (class "Default")
      (node (ref "Q4") (pin "1") (pinfunction "G_1") (pintype "passive"))
      (node (ref "R26") (pin "2") (pinfunction "2_2") (pintype "passive"))
      (node (ref "R53") (pin "1") (pinfunction "1_1") (pintype "passive"))
    )
    (net (code "24") (name "/Relay_3_Com") (class "Default")
      (node (ref "J5") (pin "2") (pinfunction "2_2") (pintype "passive"))
      (node (ref "K4") (pin "4") (pinfunction "COM_4") (pintype "passive"))
    )
    (net (code "25") (name "/Relay_3_N_Closed") (class "Default")
      (node (ref "J5") (pin "3") (pinfunction "3_3") (pintype "passive"))
      (node (ref "K4") (pin "5") (pinfunction "N_Closed_5") (pintype "passive"))
    )
    (net (code "26") (name "/Relay_3_N_Open") (class "Default")
      (node (ref "J5") (pin "1") (pinfunction "1_1") (pintype "passive"))
      (node (ref "K4") (pin "2") (pinfunction "N_Open_2") (pintype "passive"))
    )
    (net (code "27") (name "/Relay_4") (class "Default")
      (node (ref "Q3") (pin "1") (pinfunction "G_1") (pintype "passive"))
      (node (ref "R28") (pin "2") (pinfunction "2_2") (pintype "passive"))
      (node (ref "R52") (pin "1") (pinfunction "1_1") (pintype "passive"))
    )
    (net (code "28") (name "/Relay_4_Com") (class "Default")
      (node (ref "J7") (pin "2") (pinfunction "2_2") (pintype "passive"))
      (node (ref "K3") (pin "4") (pinfunction "COM_4") (pintype "passive"))
    )
    (net (code "29") (name "/Relay_4_N_Closed") (class "Default")
      (node (ref "J7") (pin "3") (pinfunction "3_3") (pintype "passive"))
      (node (ref "K3") (pin "5") (pinfunction "N_Closed_5") (pintype "passive"))
    )
    (net (code "30") (name "/Relay_4_N_Open") (class "Default")
      (node (ref "J7") (pin "1") (pinfunction "1_1") (pintype "passive"))
      (node (ref "K3") (pin "2") (pinfunction "N_Open_2") (pintype "passive"))
    )
    (net (code "31") (name "/Relay_5") (class "Default")
      (node (ref "Q5") (pin "1") (pinfunction "G_1") (pintype "passive"))
      (node (ref "R30") (pin "2") (pinfunction "2_2") (pintype "passive"))
      (node (ref "R51") (pin "1") (pinfunction "1_1") (pintype "passive"))
    )
    (net (code "32") (name "/Relay_5_Com") (class "Default")
      (node (ref "J2") (pin "2") (pinfunction "2_2") (pintype "passive"))
      (node (ref "K5") (pin "4") (pinfunction "COM_4") (pintype "passive"))
    )
    (net (code "33") (name "/Relay_5_N_Closed") (class "Default")
      (node (ref "J2") (pin "3") (pinfunction "3_3") (pintype "passive"))
      (node (ref "K5") (pin "5") (pinfunction "N_Closed_5") (pintype "passive"))
    )
    (net (code "34") (name "/Relay_5_N_Open") (class "Default")
      (node (ref "J2") (pin "1") (pinfunction "1_1") (pintype "passive"))
      (node (ref "K5") (pin "2") (pinfunction "N_Open_2") (pintype "passive"))
    )
    (net (code "35") (name "/Relay_6") (class "Default")
      (node (ref "Q6") (pin "1") (pinfunction "G_1") (pintype "passive"))
      (node (ref "R32") (pin "2") (pinfunction "2_2") (pintype "passive"))
      (node (ref "R50") (pin "1") (pinfunction "1_1") (pintype "passive"))
    )
    (net (code "36") (name "/Relay_6_Com") (class "Default")
      (node (ref "J4") (pin "2") (pinfunction "2_2") (pintype "passive"))
      (node (ref "K6") (pin "4") (pinfunction "COM_4") (pintype "passive"))
    )
    (net (code "37") (name "/Relay_6_N_Closed") (class "Default")
      (node (ref "J4") (pin "3") (pinfunction "3_3") (pintype "passive"))
      (node (ref "K6") (pin "5") (pinfunction "N_Closed_5") (pintype "passive"))
    )
    (net (code "38") (name "/Relay_6_N_Open") (class "Default")
      (node (ref "J4") (pin "1") (pinfunction "1_1") (pintype "passive"))
      (node (ref "K6") (pin "2") (pinfunction "N_Open_2") (pintype "passive"))
    )
    (net (code "39") (name "/Relay_7") (class "Default")
      (node (ref "Q8") (pin "1") (pinfunction "G_1") (pintype "passive"))
      (node (ref "R33") (pin "2") (pinfunction "2_2") (pintype "passive"))
      (node (ref "R49") (pin "1") (pinfunction "1_1") (pintype "passive"))
    )
    (net (code "40") (name "/Relay_7_Com") (class "Default")
      (node (ref "J6") (pin "2") (pinfunction "2_2") (pintype "passive"))
      (node (ref "K8") (pin "4") (pinfunction "COM_4") (pintype "passive"))
    )
    (net (code "41") (name "/Relay_7_N_Closed") (class "Default")
      (node (ref "J6") (pin "3") (pinfunction "3_3") (pintype "passive"))
      (node (ref "K8") (pin "5") (pinfunction "N_Closed_5") (pintype "passive"))
    )
    (net (code "42") (name "/Relay_7_N_Open") (class "Default")
      (node (ref "J6") (pin "1") (pinfunction "1_1") (pintype "passive"))
      (node (ref "K8") (pin "2") (pinfunction "N_Open_2") (pintype "passive"))
    )
    (net (code "43") (name "/Relay_8") (class "Default")
      (node (ref "Q7") (pin "1") (pinfunction "G_1") (pintype "passive"))
      (node (ref "R35") (pin "2") (pinfunction "2_2") (pintype "passive"))
      (node (ref "R48") (pin "1") (pinfunction "1_1") (pintype "passive"))
    )
    (net (code "44") (name "/Relay_8_Com") (class "Default")
      (node (ref "J8") (pin "2") (pinfunction "2_2") (pintype "passive"))
      (node (ref "K7") (pin "4") (pinfunction "COM_4") (pintype "passive"))
    )
    (net (code "45") (name "/Relay_8_N_Closed") (class "Default")
      (node (ref "J8") (pin "3") (pinfunction "3_3") (pintype "passive"))
      (node (ref "K7") (pin "5") (pinfunction "N_Closed_5") (pintype "passive"))
    )
    (net (code "46") (name "/Relay_8_N_Open") (class "Default")
      (node (ref "J8") (pin "1") (pinfunction "1_1") (pintype "passive"))
      (node (ref "K7") (pin "2") (pinfunction "N_Open_2") (pintype "passive"))
    )
    (net (code "47") (name "/UPDI") (class "Default")
      (node (ref "R18") (pin "2") (pinfunction "2_2") (pintype "passive"))
      (node (ref "R2") (pin "1") (pinfunction "1_1") (pintype "passive"))
    )
    (net (code "48") (name "GND") (class "Default")
      (node (ref "C1") (pin "2") (pinfunction "2_2") (pintype "passive"))
      (node (ref "C2") (pin "2") (pinfunction "2_2") (pintype "passive"))
      (node (ref "C3") (pin "2") (pinfunction "2_2") (pintype "passive"))
      (node (ref "C4") (pin "2") (pinfunction "2_2") (pintype "passive"))
      (node (ref "C5") (pin "2") (pinfunction "2_2") (pintype "passive"))
      (node (ref "C6") (pin "2") (pinfunction "2_2") (pintype "passive"))
      (node (ref "H1") (pin "13") (pinfunction "13_13") (pintype "passive"))
      (node (ref "H1") (pin "15") (pinfunction "15_15") (pintype "passive"))
      (node (ref "H2") (pin "6") (pinfunction "GND_6") (pintype "passive"))
      (node (ref "IC1") (pin "19") (pinfunction "GND_1_19") (pintype "passive"))
      (node (ref "IC1") (pin "29") (pinfunction "GND_2_29") (pintype "passive"))
      (node (ref "Q1") (pin "2") (pinfunction "S_2") (pintype "passive"))
      (node (ref "Q2") (pin "2") (pinfunction "S_2") (pintype "passive"))
      (node (ref "Q3") (pin "2") (pinfunction "S_2") (pintype "passive"))
      (node (ref "Q4") (pin "2") (pinfunction "S_2") (pintype "passive"))
      (node (ref "Q5") (pin "2") (pinfunction "S_2") (pintype "passive"))
      (node (ref "Q6") (pin "2") (pinfunction "S_2") (pintype "passive"))
      (node (ref "Q7") (pin "2") (pinfunction "S_2") (pintype "passive"))
      (node (ref "Q8") (pin "2") (pinfunction "S_2") (pintype "passive"))
      (node (ref "R48") (pin "2") (pinfunction "2_2") (pintype "passive"))
      (node (ref "R49") (pin "2") (pinfunction "2_2") (pintype "passive"))
      (node (ref "R50") (pin "2") (pinfunction "2_2") (pintype "passive"))
      (node (ref "R51") (pin "2") (pinfunction "2_2") (pintype "passive"))
      (node (ref "R52") (pin "2") (pinfunction "2_2") (pintype "passive"))
      (node (ref "R53") (pin "2") (pinfunction "2_2") (pintype "passive"))
      (node (ref "R54") (pin "2") (pinfunction "2_2") (pintype "passive"))
      (node (ref "R55") (pin "2") (pinfunction "2_2") (pintype "passive"))
    )
    (net (code "49") (name "Net-(D1-A)") (class "Default")
      (node (ref "D1") (pin "2") (pinfunction "A_2") (pintype "passive"))
      (node (ref "K2") (pin "1") (pinfunction "COIL_1_1") (pintype "passive"))
      (node (ref "LED2") (pin "1") (pinfunction "K_1") (pintype "passive"))
      (node (ref "Q2") (pin "3") (pinfunction "D_3") (pintype "passive"))
    )
    (net (code "50") (name "Net-(D2-A)") (class "Default")
      (node (ref "D2") (pin "2") (pinfunction "A_2") (pintype "passive"))
      (node (ref "K3") (pin "1") (pinfunction "COIL_1_1") (pintype "passive"))
      (node (ref "LED3") (pin "1") (pinfunction "K_1") (pintype "passive"))
      (node (ref "Q3") (pin "3") (pinfunction "D_3") (pintype "passive"))
    )
    (net (code "51") (name "Net-(D3-A)") (class "Default")
      (node (ref "D3") (pin "2") (pinfunction "A_2") (pintype "passive"))
      (node (ref "K1") (pin "1") (pinfunction "COIL_1_1") (pintype "passive"))
      (node (ref "LED1") (pin "1") (pinfunction "K_1") (pintype "passive"))
      (node (ref "Q1") (pin "3") (pinfunction "D_3") (pintype "passive"))
    )
    (net (code "52") (name "Net-(D4-A)") (class "Default")
      (node (ref "D4") (pin "2") (pinfunction "A_2") (pintype "passive"))
      (node (ref "K4") (pin "1") (pinfunction "COIL_1_1") (pintype "passive"))
      (node (ref "LED4") (pin "1") (pinfunction "K_1") (pintype "passive"))
      (node (ref "Q4") (pin "3") (pinfunction "D_3") (pintype "passive"))
    )
    (net (code "53") (name "Net-(D5-A)") (class "Default")
      (node (ref "D5") (pin "2") (pinfunction "A_2") (pintype "passive"))
      (node (ref "K5") (pin "1") (pinfunction "COIL_1_1") (pintype "passive"))
      (node (ref "LED5") (pin "1") (pinfunction "K_1") (pintype "passive"))
      (node (ref "Q5") (pin "3") (pinfunction "D_3") (pintype "passive"))
    )
    (net (code "54") (name "Net-(D6-A)") (class "Default")
      (node (ref "D6") (pin "2") (pinfunction "A_2") (pintype "passive"))
      (node (ref "K6") (pin "1") (pinfunction "COIL_1_1") (pintype "passive"))
      (node (ref "LED6") (pin "1") (pinfunction "K_1") (pintype "passive"))
      (node (ref "Q6") (pin "3") (pinfunction "D_3") (pintype "passive"))
    )
    (net (code "55") (name "Net-(D7-A)") (class "Default")
      (node (ref "D7") (pin "2") (pinfunction "A_2") (pintype "passive"))
      (node (ref "K7") (pin "1") (pinfunction "COIL_1_1") (pintype "passive"))
      (node (ref "LED7") (pin "1") (pinfunction "K_1") (pintype "passive"))
      (node (ref "Q7") (pin "3") (pinfunction "D_3") (pintype "passive"))
    )
    (net (code "56") (name "Net-(D8-A)") (class "Default")
      (node (ref "D8") (pin "2") (pinfunction "A_2") (pintype "passive"))
      (node (ref "K8") (pin "1") (pinfunction "COIL_1_1") (pintype "passive"))
      (node (ref "LED8") (pin "1") (pinfunction "K_1") (pintype "passive"))
      (node (ref "Q8") (pin "3") (pinfunction "D_3") (pintype "passive"))
    )
    (net (code "57") (name "Net-(H1-Pad2)") (class "Default")
      (node (ref "H1") (pin "2") (pinfunction "2_2") (pintype "passive"))
      (node (ref "R1") (pin "2") (pinfunction "2_2") (pintype "passive"))
    )
    (net (code "58") (name "Net-(H1-Pad4)") (class "Default")
      (node (ref "H1") (pin "4") (pinfunction "4_4") (pintype "passive"))
      (node (ref "R3") (pin "2") (pinfunction "2_2") (pintype "passive"))
    )
    (net (code "59") (name "Net-(H1-Pad5)") (class "Default")
      (node (ref "H1") (pin "5") (pinfunction "5_5") (pintype "passive"))
      (node (ref "R7") (pin "1") (pinfunction "1_1") (pintype "passive"))
    )
    (net (code "60") (name "Net-(H1-Pad6)") (class "Default")
      (node (ref "H1") (pin "6") (pinfunction "6_6") (pintype "passive"))
      (node (ref "R6") (pin "2") (pinfunction "2_2") (pintype "passive"))
    )
    (net (code "61") (name "Net-(H1-Pad7)") (class "Default")
      (node (ref "H1") (pin "7") (pinfunction "7_7") (pintype "passive"))
      (node (ref "R10") (pin "1") (pinfunction "1_1") (pintype "passive"))
    )
    (net (code "62") (name "Net-(H1-Pad8)") (class "Default")
      (node (ref "H1") (pin "8") (pinfunction "8_8") (pintype "passive"))
      (node (ref "R9") (pin "2") (pinfunction "2_2") (pintype "passive"))
    )
    (net (code "63") (name "Net-(H1-Pad9)") (class "Default")
      (node (ref "H1") (pin "9") (pinfunction "9_9") (pintype "passive"))
      (node (ref "R12") (pin "1") (pinfunction "1_1") (pintype "passive"))
    )
    (net (code "64") (name "Net-(H1-Pad10)") (class "Default")
      (node (ref "H1") (pin "10") (pinfunction "10_10") (pintype "passive"))
      (node (ref "R11") (pin "2") (pinfunction "2_2") (pintype "passive"))
    )
    (net (code "65") (name "Net-(H1-Pad11)") (class "Default")
      (node (ref "H1") (pin "11") (pinfunction "11_11") (pintype "passive"))
      (node (ref "R14") (pin "1") (pinfunction "1_1") (pintype "passive"))
    )
    (net (code "66") (name "Net-(H1-Pad12)") (class "Default")
      (node (ref "H1") (pin "12") (pinfunction "12_12") (pintype "passive"))
      (node (ref "R13") (pin "2") (pinfunction "2_2") (pintype "passive"))
    )
    (net (code "67") (name "Net-(H1-Pad14)") (class "Default")
      (node (ref "H1") (pin "14") (pinfunction "14_14") (pintype "passive"))
      (node (ref "R15") (pin "2") (pinfunction "2_2") (pintype "passive"))
    )
    (net (code "68") (name "Net-(H1-Pad16)") (class "Default")
      (node (ref "H1") (pin "16") (pinfunction "16_16") (pintype "passive"))
      (node (ref "R16") (pin "2") (pinfunction "2_2") (pintype "passive"))
    )
    (net (code "69") (name "Net-(H2-NC-Pad3)") (class "Default")
      (node (ref "H2") (pin "3") (pinfunction "NC_3") (pintype "passive"))
      (node (ref "R4") (pin "2") (pinfunction "2_2") (pintype "passive"))
    )
    (net (code "70") (name "Net-(H2-NC-Pad4)") (class "Default")
      (node (ref "H2") (pin "4") (pinfunction "NC_4") (pintype "passive"))
      (node (ref "R5") (pin "1") (pinfunction "1_1") (pintype "passive"))
    )
    (net (code "71") (name "Net-(H2-NC-Pad5)") (class "Default")
      (node (ref "H2") (pin "5") (pinfunction "NC_5") (pintype "passive"))
      (node (ref "R8") (pin "2") (pinfunction "2_2") (pintype "passive"))
    )
    (net (code "72") (name "Net-(H2-UDPI)") (class "Default")
      (node (ref "H2") (pin "1") (pinfunction "UDPI_1") (pintype "passive"))
      (node (ref "R2") (pin "2") (pinfunction "2_2") (pintype "passive"))
    )
    (net (code "73") (name "Net-(IC1-PA0)") (class "Default")
      (node (ref "IC1") (pin "30") (pinfunction "PA0_30") (pintype "passive"))
      (node (ref "R17") (pin "2") (pinfunction "2_2") (pintype "passive"))
    )
    (net (code "74") (name "Net-(IC1-PA1)") (class "Default")
      (node (ref "IC1") (pin "31") (pinfunction "PA1_31") (pintype "passive"))
      (node (ref "R19") (pin "2") (pinfunction "2_2") (pintype "passive"))
    )
    (net (code "75") (name "Net-(IC1-PA2)") (class "Default")
      (node (ref "IC1") (pin "32") (pinfunction "PA2_32") (pintype "passive"))
      (node (ref "R21") (pin "2") (pinfunction "2_2") (pintype "passive"))
    )
    (net (code "76") (name "Net-(IC1-PA3)") (class "Default")
      (node (ref "IC1") (pin "1") (pinfunction "PA3_1") (pintype "passive"))
      (node (ref "R23") (pin "2") (pinfunction "2_2") (pintype "passive"))
    )
    (net (code "77") (name "Net-(IC1-PA4)") (class "Default")
      (node (ref "IC1") (pin "2") (pinfunction "PA4_2") (pintype "passive"))
      (node (ref "R25") (pin "2") (pinfunction "2_2") (pintype "passive"))
    )
    (net (code "78") (name "Net-(IC1-PA5)") (class "Default")
      (node (ref "IC1") (pin "3") (pinfunction "PA5_3") (pintype "passive"))
      (node (ref "R27") (pin "2") (pinfunction "2_2") (pintype "passive"))
    )
    (net (code "79") (name "Net-(IC1-PA6)") (class "Default")
      (node (ref "IC1") (pin "4") (pinfunction "PA6_4") (pintype "passive"))
      (node (ref "R29") (pin "2") (pinfunction "2_2") (pintype "passive"))
    )
    (net (code "80") (name "Net-(IC1-PA7)") (class "Default")
      (node (ref "IC1") (pin "5") (pinfunction "PA7_5") (pintype "passive"))
      (node (ref "R31") (pin "2") (pinfunction "2_2") (pintype "passive"))
    )
    (net (code "81") (name "Net-(IC1-PC0)") (class "Default")
      (node (ref "IC1") (pin "6") (pinfunction "PC0_6") (pintype "passive"))
      (node (ref "R34") (pin "2") (pinfunction "2_2") (pintype "passive"))
    )
    (net (code "82") (name "Net-(IC1-PC1)") (class "Default")
      (node (ref "IC1") (pin "7") (pinfunction "PC1_7") (pintype "passive"))
      (node (ref "R36") (pin "2") (pinfunction "2_2") (pintype "passive"))
    )
    (net (code "83") (name "Net-(IC1-PC2)") (class "Default")
      (node (ref "IC1") (pin "8") (pinfunction "PC2_8") (pintype "passive"))
      (node (ref "R38") (pin "2") (pinfunction "2_2") (pintype "passive"))
    )
    (net (code "84") (name "Net-(IC1-PC3)") (class "Default")
      (node (ref "IC1") (pin "9") (pinfunction "PC3_9") (pintype "passive"))
      (node (ref "R40") (pin "2") (pinfunction "2_2") (pintype "passive"))
    )
    (net (code "85") (name "Net-(IC1-PD3)") (class "Default")
      (node (ref "IC1") (pin "13") (pinfunction "PD3_13") (pintype "passive"))
      (node (ref "R41") (pin "1") (pinfunction "1_1") (pintype "passive"))
    )
    (net (code "86") (name "Net-(IC1-PD4)") (class "Default")
      (node (ref "IC1") (pin "14") (pinfunction "PD4_14") (pintype "passive"))
      (node (ref "R39") (pin "1") (pinfunction "1_1") (pintype "passive"))
    )
    (net (code "87") (name "Net-(IC1-PD5)") (class "Default")
      (node (ref "IC1") (pin "15") (pinfunction "PD5_15") (pintype "passive"))
      (node (ref "R37") (pin "1") (pinfunction "1_1") (pintype "passive"))
    )
    (net (code "88") (name "Net-(IC1-PD6)") (class "Default")
      (node (ref "IC1") (pin "16") (pinfunction "PD6_16") (pintype "passive"))
      (node (ref "R35") (pin "1") (pinfunction "1_1") (pintype "passive"))
    )
    (net (code "89") (name "Net-(IC1-PD7)") (class "Default")
      (node (ref "IC1") (pin "17") (pinfunction "PD7_17") (pintype "passive"))
      (node (ref "R33") (pin "1") (pinfunction "1_1") (pintype "passive"))
    )
    (net (code "90") (name "Net-(IC1-PD~{1})") (class "Default")
      (node (ref "IC1") (pin "11") (pinfunction "PD~{1}_11") (pintype "passive"))
      (node (ref "R43") (pin "1") (pinfunction "1_1") (pintype "passive"))
    )
    (net (code "91") (name "Net-(IC1-PD~{2})") (class "Default")
      (node (ref "IC1") (pin "12") (pinfunction "PD~{2}_12") (pintype "passive"))
      (node (ref "R42") (pin "1") (pinfunction "1_1") (pintype "passive"))
    )
    (net (code "92") (name "Net-(IC1-PF0)") (class "Default")
      (node (ref "IC1") (pin "20") (pinfunction "PF0_20") (pintype "passive"))
      (node (ref "R32") (pin "1") (pinfunction "1_1") (pintype "passive"))
    )
    (net (code "93") (name "Net-(IC1-PF1)") (class "Default")
      (node (ref "IC1") (pin "21") (pinfunction "PF1_21") (pintype "passive"))
      (node (ref "R30") (pin "1") (pinfunction "1_1") (pintype "passive"))
    )
    (net (code "94") (name "Net-(IC1-PF2)") (class "Default")
      (node (ref "IC1") (pin "22") (pinfunction "PF2_22") (pintype "passive"))
      (node (ref "R28") (pin "1") (pinfunction "1_1") (pintype "passive"))
    )
    (net (code "95") (name "Net-(IC1-PF3)") (class "Default")
      (node (ref "IC1") (pin "23") (pinfunction "PF3_23") (pintype "passive"))
      (node (ref "R26") (pin "1") (pinfunction "1_1") (pintype "passive"))
    )
    (net (code "96") (name "Net-(IC1-PF4)") (class "Default")
      (node (ref "IC1") (pin "24") (pinfunction "PF4_24") (pintype "passive"))
      (node (ref "R24") (pin "1") (pinfunction "1_1") (pintype "passive"))
    )
    (net (code "97") (name "Net-(IC1-PF5)") (class "Default")
      (node (ref "IC1") (pin "25") (pinfunction "PF5_25") (pintype "passive"))
      (node (ref "R22") (pin "1") (pinfunction "1_1") (pintype "passive"))
    )
    (net (code "98") (name "Net-(IC1-PF6_(~{RESET)})") (class "Default")
      (node (ref "IC1") (pin "26") (pinfunction "PF6_(~{RESET)}_26") (pintype "passive"))
      (node (ref "R20") (pin "1") (pinfunction "1_1") (pintype "passive"))
    )
    (net (code "99") (name "Net-(IC1-PF7_(UPDI))") (class "Default")
      (node (ref "IC1") (pin "27") (pinfunction "PF7_(UPDI)_27") (pintype "passive"))
      (node (ref "R18") (pin "1") (pinfunction "1_1") (pintype "passive"))
    )
    (net (code "100") (name "Net-(LED1-A)") (class "Default")
      (node (ref "LED1") (pin "2") (pinfunction "A_2") (pintype "passive"))
      (node (ref "R44") (pin "1") (pinfunction "1_1") (pintype "passive"))
    )
    (net (code "101") (name "Net-(LED2-A)") (class "Default")
      (node (ref "LED2") (pin "2") (pinfunction "A_2") (pintype "passive"))
      (node (ref "R45") (pin "1") (pinfunction "1_1") (pintype "passive"))
    )
    (net (code "102") (name "Net-(LED3-A)") (class "Default")
      (node (ref "LED3") (pin "2") (pinfunction "A_2") (pintype "passive"))
      (node (ref "R46") (pin "1") (pinfunction "1_1") (pintype "passive"))
    )
    (net (code "103") (name "Net-(LED4-A)") (class "Default")
      (node (ref "LED4") (pin "2") (pinfunction "A_2") (pintype "passive"))
      (node (ref "R47") (pin "1") (pinfunction "1_1") (pintype "passive"))
    )
    (net (code "104") (name "Net-(LED5-A)") (class "Default")
      (node (ref "LED5") (pin "2") (pinfunction "A_2") (pintype "passive"))
      (node (ref "R56") (pin "1") (pinfunction "1_1") (pintype "passive"))
    )
    (net (code "105") (name "Net-(LED6-A)") (class "Default")
      (node (ref "LED6") (pin "2") (pinfunction "A_2") (pintype "passive"))
      (node (ref "R57") (pin "1") (pinfunction "1_1") (pintype "passive"))
    )
    (net (code "106") (name "Net-(LED7-A)") (class "Default")
      (node (ref "LED7") (pin "2") (pinfunction "A_2") (pintype "passive"))
      (node (ref "R58") (pin "1") (pinfunction "1_1") (pintype "passive"))
    )
    (net (code "107") (name "Net-(LED8-A)") (class "Default")
      (node (ref "LED8") (pin "2") (pinfunction "A_2") (pintype "passive"))
      (node (ref "R59") (pin "1") (pinfunction "1_1") (pintype "passive"))
    )
    (net (code "108") (name "Net-(R4-Pad1)") (class "Default")
      (node (ref "R4") (pin "1") (pinfunction "1_1") (pintype "passive"))
      (node (ref "TP2") (pin "1") (pinfunction "1_1") (pintype "passive"))
    )
    (net (code "109") (name "Net-(R5-Pad2)") (class "Default")
      (node (ref "R5") (pin "2") (pinfunction "2_2") (pintype "passive"))
      (node (ref "TP3") (pin "1") (pinfunction "1_1") (pintype "passive"))
    )
    (net (code "110") (name "Net-(R8-Pad1)") (class "Default")
      (node (ref "R8") (pin "1") (pinfunction "1_1") (pintype "passive"))
      (node (ref "TP4") (pin "1") (pinfunction "1_1") (pintype "passive"))
    )
    (net (code "111") (name "Net-(R34-Pad1)") (class "Default")
      (node (ref "R34") (pin "1") (pinfunction "1_1") (pintype "passive"))
      (node (ref "TP5") (pin "1") (pinfunction "1_1") (pintype "passive"))
    )
    (net (code "112") (name "Net-(R36-Pad1)") (class "Default")
      (node (ref "R36") (pin "1") (pinfunction "1_1") (pintype "passive"))
      (node (ref "TP6") (pin "1") (pinfunction "1_1") (pintype "passive"))
    )
    (net (code "113") (name "Net-(R37-Pad2)") (class "Default")
      (node (ref "R37") (pin "2") (pinfunction "2_2") (pintype "passive"))
      (node (ref "TP7") (pin "1") (pinfunction "1_1") (pintype "passive"))
    )
    (net (code "114") (name "Net-(R38-Pad1)") (class "Default")
      (node (ref "R38") (pin "1") (pinfunction "1_1") (pintype "passive"))
      (node (ref "TP8") (pin "1") (pinfunction "1_1") (pintype "passive"))
    )
    (net (code "115") (name "Net-(R39-Pad2)") (class "Default")
      (node (ref "R39") (pin "2") (pinfunction "2_2") (pintype "passive"))
      (node (ref "TP9") (pin "1") (pinfunction "1_1") (pintype "passive"))
    )
    (net (code "116") (name "Net-(R40-Pad1)") (class "Default")
      (node (ref "R40") (pin "1") (pinfunction "1_1") (pintype "passive"))
      (node (ref "TP10") (pin "1") (pinfunction "1_1") (pintype "passive"))
    )
  )
)
